# CarrierRecovery.net
KiCad netlist of a schematic drawn in Altium Designer
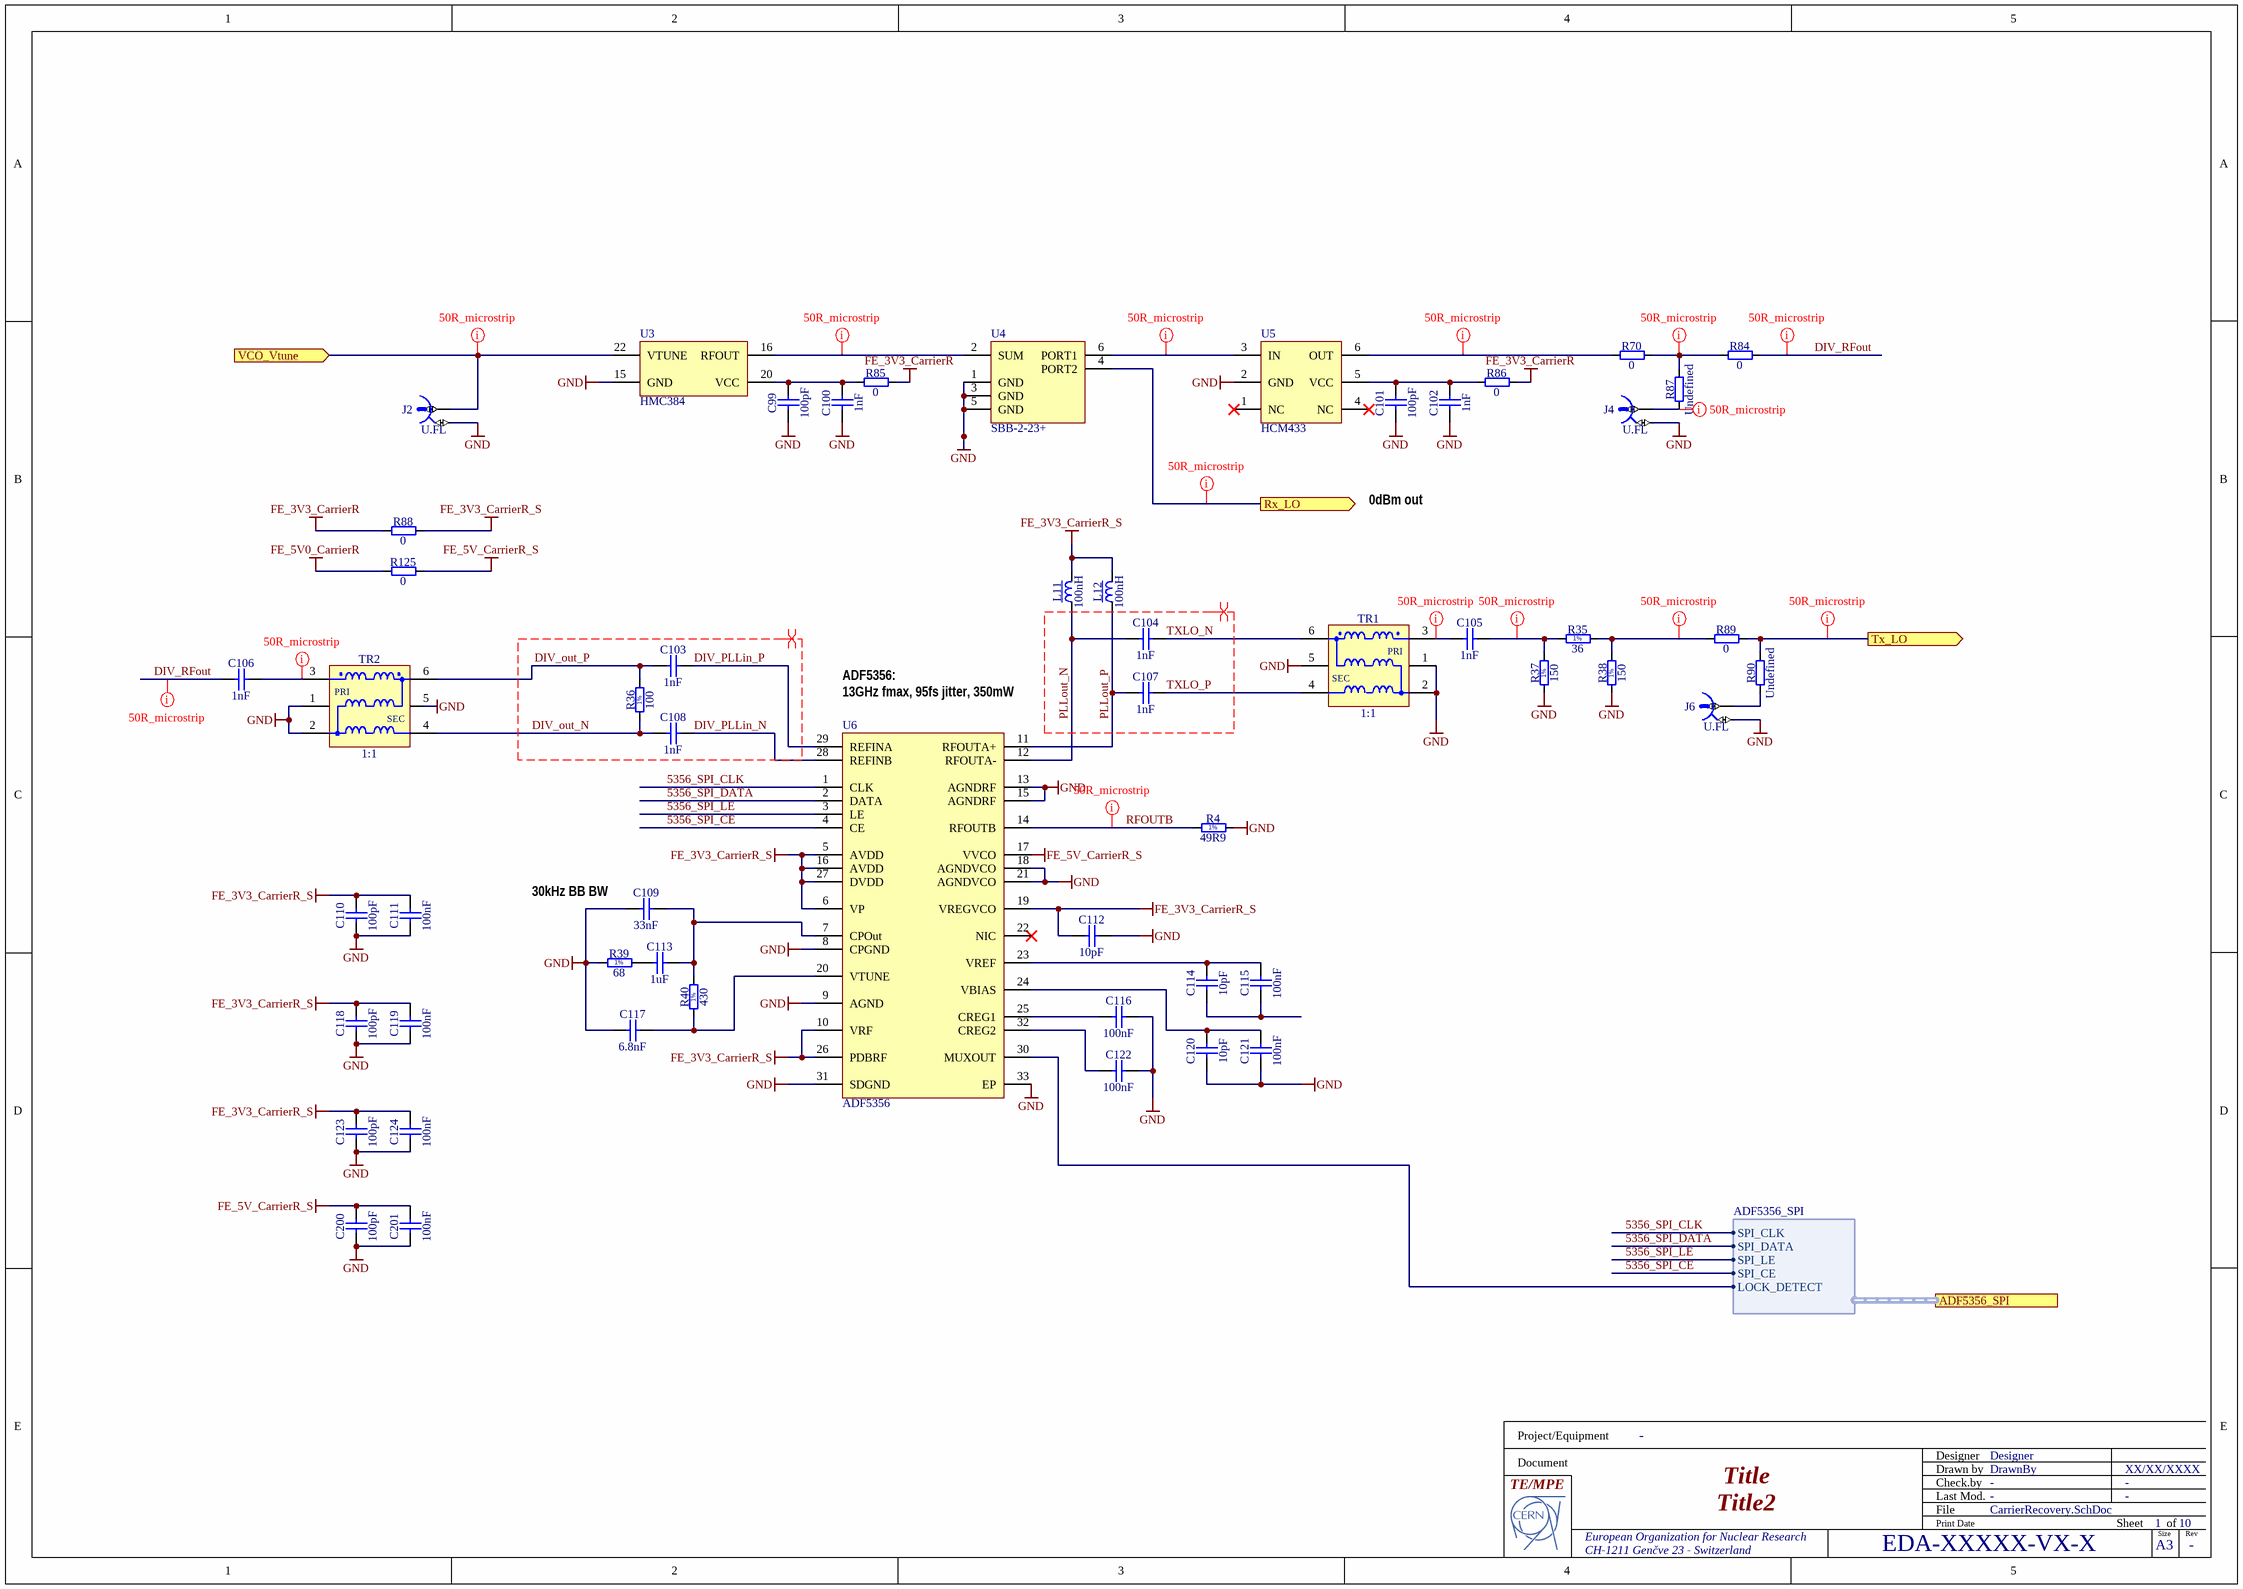
[diagram p0: CarrierRecovery.SchDoc]

(export (version "E")
  (design (tool "Eeschema 10.0.6"))
  (components
    (comp (ref "C99")
      (value "100pF")
      (footprint "CAPC1005X55N")
      (description "Non-polarised capacitor")
      (fields
        (field (name "PART NUMBER") "CC0402_100PF_50V_5%_C0G")
        (field (name "VOLTAGE") "50V")
        (field (name "AUTHOR") "CERN DEM JLC")
      )
      (libsource (lib "Capacitors") (part "Capacitor - non polarized"))
    )
    (comp (ref "C100")
      (value "1nF")
      (footprint "CAPC1005X55N")
      (description "Non-polarised capacitor")
      (fields
        (field (name "PART NUMBER") "CC0402_1NF_50V_10%_X7R")
        (field (name "VOLTAGE") "50V")
        (field (name "AUTHOR") "CERN DEM JLC")
      )
      (libsource (lib "Capacitors") (part "Capacitor - non polarized"))
    )
    (comp (ref "C101")
      (value "100pF")
      (footprint "CAPC1005X55N")
      (description "Non-polarised capacitor")
      (fields
        (field (name "PART NUMBER") "CC0402_100PF_50V_5%_C0G")
        (field (name "VOLTAGE") "50V")
        (field (name "AUTHOR") "CERN DEM JLC")
      )
      (libsource (lib "Capacitors") (part "Capacitor - non polarized"))
    )
    (comp (ref "C102")
      (value "1nF")
      (footprint "CAPC1005X55N")
      (description "Non-polarised capacitor")
      (fields
        (field (name "PART NUMBER") "CC0402_1NF_50V_10%_X7R")
        (field (name "VOLTAGE") "50V")
        (field (name "AUTHOR") "CERN DEM JLC")
      )
      (libsource (lib "Capacitors") (part "Capacitor - non polarized"))
    )
    (comp (ref "C103")
      (value "1nF")
      (footprint "CAPC1005X55N")
      (description "Non-polarised capacitor")
      (fields
        (field (name "PART NUMBER") "CC0402_1NF_50V_10%_X7R")
        (field (name "VOLTAGE") "50V")
        (field (name "AUTHOR") "CERN DEM JLC")
      )
      (libsource (lib "Capacitors") (part "Capacitor - non polarized"))
    )
    (comp (ref "C104")
      (value "1nF")
      (footprint "CAPC1005X55N")
      (description "Non-polarised capacitor")
      (fields
        (field (name "PART NUMBER") "CC0402_1NF_50V_10%_X7R")
        (field (name "VOLTAGE") "50V")
        (field (name "AUTHOR") "CERN DEM JLC")
      )
      (libsource (lib "Capacitors") (part "Capacitor - non polarized"))
    )
    (comp (ref "C105")
      (value "1nF")
      (footprint "CAPC1005X55N")
      (description "Non-polarised capacitor")
      (fields
        (field (name "PART NUMBER") "CC0402_1NF_50V_10%_X7R")
        (field (name "VOLTAGE") "50V")
        (field (name "AUTHOR") "CERN DEM JLC")
      )
      (libsource (lib "Capacitors") (part "Capacitor - non polarized"))
    )
    (comp (ref "C106")
      (value "1nF")
      (footprint "CAPC1005X55N")
      (description "Non-polarised capacitor")
      (fields
        (field (name "PART NUMBER") "CC0402_1NF_50V_10%_X7R")
        (field (name "VOLTAGE") "50V")
        (field (name "AUTHOR") "CERN DEM JLC")
      )
      (libsource (lib "Capacitors") (part "Capacitor - non polarized"))
    )
    (comp (ref "C107")
      (value "1nF")
      (footprint "CAPC1005X55N")
      (description "Non-polarised capacitor")
      (fields
        (field (name "PART NUMBER") "CC0402_1NF_50V_10%_X7R")
        (field (name "VOLTAGE") "50V")
        (field (name "AUTHOR") "CERN DEM JLC")
      )
      (libsource (lib "Capacitors") (part "Capacitor - non polarized"))
    )
    (comp (ref "C108")
      (value "1nF")
      (footprint "CAPC1005X55N")
      (description "Non-polarised capacitor")
      (fields
        (field (name "PART NUMBER") "CC0402_1NF_50V_10%_X7R")
        (field (name "VOLTAGE") "50V")
        (field (name "AUTHOR") "CERN DEM JLC")
      )
      (libsource (lib "Capacitors") (part "Capacitor - non polarized"))
    )
    (comp (ref "C109")
      (value "33nF")
      (footprint "CAPC2012X135N")
      (description "Non-polarised capacitor")
      (fields
        (field (name "PART NUMBER") "CC0805_33NF_25V_10%_X7R")
        (field (name "VOLTAGE") "25V")
        (field (name "AUTHOR") "CERN DEM JLC")
      )
      (libsource (lib "Capacitors") (part "Capacitor - non polarized"))
    )
    (comp (ref "C110")
      (value "100pF")
      (footprint "CAPC1005X55N")
      (description "Non-polarised capacitor")
      (fields
        (field (name "PART NUMBER") "CC0402_100PF_50V_5%_C0G")
        (field (name "VOLTAGE") "50V")
        (field (name "AUTHOR") "CERN DEM JLC")
      )
      (libsource (lib "Capacitors") (part "Capacitor - non polarized"))
    )
    (comp (ref "C111")
      (value "100nF")
      (footprint "CAPC1005X55N")
      (description "Non-polarised capacitor")
      (fields
        (field (name "PART NUMBER") "CC0402_100NF_50V_10%_X7R")
        (field (name "VOLTAGE") "50V")
        (field (name "AUTHOR") "CERN DEM MR")
      )
      (libsource (lib "Capacitors") (part "Capacitor - non polarized"))
    )
    (comp (ref "C112")
      (value "10pF")
      (footprint "CAPC1005X55N")
      (description "Non-polarised capacitor")
      (fields
        (field (name "PART NUMBER") "CC0402_10PF_50V_5%_C0G")
        (field (name "VOLTAGE") "50V")
        (field (name "AUTHOR") "CERN DEM JLC")
      )
      (libsource (lib "Capacitors") (part "Capacitor - non polarized"))
    )
    (comp (ref "C113")
      (value "1uF")
      (footprint "CAPC3216X140N")
      (description "Non-polarised capacitor")
      (fields
        (field (name "PART NUMBER") "CC1206_1UF_25V_10%_X7R")
        (field (name "VOLTAGE") "25V")
        (field (name "AUTHOR") "CERN DEM JLC")
      )
      (libsource (lib "Capacitors") (part "Capacitor - non polarized"))
    )
    (comp (ref "C114")
      (value "10pF")
      (footprint "CAPC1005X55N")
      (description "Non-polarised capacitor")
      (fields
        (field (name "PART NUMBER") "CC0402_10PF_50V_5%_C0G")
        (field (name "VOLTAGE") "50V")
        (field (name "AUTHOR") "CERN DEM JLC")
      )
      (libsource (lib "Capacitors") (part "Capacitor - non polarized"))
    )
    (comp (ref "C115")
      (value "100nF")
      (footprint "CAPC1005X55N")
      (description "Non-polarised capacitor")
      (fields
        (field (name "PART NUMBER") "CC0402_100NF_50V_10%_X7R")
        (field (name "VOLTAGE") "50V")
        (field (name "AUTHOR") "CERN DEM MR")
      )
      (libsource (lib "Capacitors") (part "Capacitor - non polarized"))
    )
    (comp (ref "C116")
      (value "100nF")
      (footprint "CAPC1005X55N")
      (description "Non-polarised capacitor")
      (fields
        (field (name "PART NUMBER") "CC0402_100NF_50V_10%_X7R")
        (field (name "VOLTAGE") "50V")
        (field (name "AUTHOR") "CERN DEM MR")
      )
      (libsource (lib "Capacitors") (part "Capacitor - non polarized"))
    )
    (comp (ref "C117")
      (value "6.8nF")
      (footprint "CAPC2012X135N")
      (description "Non-polarised capacitor")
      (fields
        (field (name "PART NUMBER") "CC0805_6.8NF_50V_10%_X7R")
        (field (name "VOLTAGE") "50V")
        (field (name "AUTHOR") "CERN DEM JLC")
      )
      (libsource (lib "Capacitors") (part "Capacitor - non polarized"))
    )
    (comp (ref "C118")
      (value "100pF")
      (footprint "CAPC1005X55N")
      (description "Non-polarised capacitor")
      (fields
        (field (name "PART NUMBER") "CC0402_100PF_50V_5%_C0G")
        (field (name "VOLTAGE") "50V")
        (field (name "AUTHOR") "CERN DEM JLC")
      )
      (libsource (lib "Capacitors") (part "Capacitor - non polarized"))
    )
    (comp (ref "C119")
      (value "100nF")
      (footprint "CAPC1005X55N")
      (description "Non-polarised capacitor")
      (fields
        (field (name "PART NUMBER") "CC0402_100NF_50V_10%_X7R")
        (field (name "VOLTAGE") "50V")
        (field (name "AUTHOR") "CERN DEM MR")
      )
      (libsource (lib "Capacitors") (part "Capacitor - non polarized"))
    )
    (comp (ref "C120")
      (value "10pF")
      (footprint "CAPC1005X55N")
      (description "Non-polarised capacitor")
      (fields
        (field (name "PART NUMBER") "CC0402_10PF_50V_5%_C0G")
        (field (name "VOLTAGE") "50V")
        (field (name "AUTHOR") "CERN DEM JLC")
      )
      (libsource (lib "Capacitors") (part "Capacitor - non polarized"))
    )
    (comp (ref "C121")
      (value "100nF")
      (footprint "CAPC1005X55N")
      (description "Non-polarised capacitor")
      (fields
        (field (name "PART NUMBER") "CC0402_100NF_50V_10%_X7R")
        (field (name "VOLTAGE") "50V")
        (field (name "AUTHOR") "CERN DEM MR")
      )
      (libsource (lib "Capacitors") (part "Capacitor - non polarized"))
    )
    (comp (ref "C122")
      (value "100nF")
      (footprint "CAPC1005X55N")
      (description "Non-polarised capacitor")
      (fields
        (field (name "PART NUMBER") "CC0402_100NF_50V_10%_X7R")
        (field (name "VOLTAGE") "50V")
        (field (name "AUTHOR") "CERN DEM MR")
      )
      (libsource (lib "Capacitors") (part "Capacitor - non polarized"))
    )
    (comp (ref "C123")
      (value "100pF")
      (footprint "CAPC1005X55N")
      (description "Non-polarised capacitor")
      (fields
        (field (name "PART NUMBER") "CC0402_100PF_50V_5%_C0G")
        (field (name "VOLTAGE") "50V")
        (field (name "AUTHOR") "CERN DEM JLC")
      )
      (libsource (lib "Capacitors") (part "Capacitor - non polarized"))
    )
    (comp (ref "C124")
      (value "100nF")
      (footprint "CAPC1005X55N")
      (description "Non-polarised capacitor")
      (fields
        (field (name "PART NUMBER") "CC0402_100NF_50V_10%_X7R")
        (field (name "VOLTAGE") "50V")
        (field (name "AUTHOR") "CERN DEM MR")
      )
      (libsource (lib "Capacitors") (part "Capacitor - non polarized"))
    )
    (comp (ref "C200")
      (value "100pF")
      (footprint "CAPC1005X55N")
      (description "Non-polarised capacitor")
      (fields
        (field (name "PART NUMBER") "CC0402_100PF_50V_5%_C0G")
        (field (name "VOLTAGE") "50V")
        (field (name "AUTHOR") "CERN DEM JLC")
      )
      (libsource (lib "Capacitors") (part "Capacitor - non polarized"))
    )
    (comp (ref "C201")
      (value "100nF")
      (footprint "CAPC1005X55N")
      (description "Non-polarised capacitor")
      (fields
        (field (name "PART NUMBER") "CC0402_100NF_50V_10%_X7R")
        (field (name "VOLTAGE") "50V")
        (field (name "AUTHOR") "CERN DEM MR")
      )
      (libsource (lib "Capacitors") (part "Capacitor - non polarized"))
    )
    (comp (ref "J2")
      (value "U.FL")
      (footprint "HIROSE_U.FL-R-SMT-1(10)")
      (fields
        (field (name "PART NUMBER") "HIROSE_U.FL-R-SMT-1(10)")
        (field (name "MANUFACTURER") "HIROSE (HRS)")
        (field (name "MANUFACTURER PART NUMBER") "U.FL-R-SMT-1(10)")
        (field (name "AUTHOR") "CERN DEM JLC")
      )
      (libsource (lib "Connectors") (part "Coax_1Male_1Shield"))
    )
    (comp (ref "J4")
      (value "U.FL")
      (footprint "HIROSE_U.FL-R-SMT-1(10)")
      (fields
        (field (name "PART NUMBER") "HIROSE_U.FL-R-SMT-1(10)")
        (field (name "MANUFACTURER") "HIROSE (HRS)")
        (field (name "MANUFACTURER PART NUMBER") "U.FL-R-SMT-1(10)")
        (field (name "AUTHOR") "CERN DEM JLC")
      )
      (libsource (lib "Connectors") (part "Coax_1Male_1Shield"))
    )
    (comp (ref "J6")
      (value "U.FL")
      (footprint "HIROSE_U.FL-R-SMT-1(10)")
      (fields
        (field (name "PART NUMBER") "HIROSE_U.FL-R-SMT-1(10)")
        (field (name "MANUFACTURER") "HIROSE (HRS)")
        (field (name "MANUFACTURER PART NUMBER") "U.FL-R-SMT-1(10)")
        (field (name "AUTHOR") "CERN DEM JLC")
      )
      (libsource (lib "Connectors") (part "Coax_1Male_1Shield"))
    )
    (comp (ref "L11")
      (value "100nH")
      (footprint "IND_COILCRAFT_0603HP")
      (description "Inductor With Core")
      (fields
        (field (name "PART NUMBER") "IND0603_100NH_2%_COILCRAFT_0603HP-R10XGLU")
        (field (name "POWER") "470mA")
        (field (name "AUTHOR") "CERN DEM JLC")
      )
      (libsource (lib "Inductors & Transformers") (part "Inductor With Magnetic core"))
    )
    (comp (ref "L12")
      (value "100nH")
      (footprint "IND_COILCRAFT_0603HP")
      (description "Inductor With Core")
      (fields
        (field (name "PART NUMBER") "IND0603_100NH_2%_COILCRAFT_0603HP-R10XGLU")
        (field (name "POWER") "470mA")
        (field (name "AUTHOR") "CERN DEM JLC")
      )
      (libsource (lib "Inductors & Transformers") (part "Inductor With Magnetic core"))
    )
    (comp (ref "R4")
      (value "49R9")
      (footprint "RESC1005X40N")
      (description "Resistor - 1%")
      (fields
        (field (name "PART NUMBER") "R0402_49R9_1%_0.0625W_100PPM")
        (field (name "POWER") "0.0625W")
        (field (name "AUTHOR") "CERN DEM JLC")
      )
      (libsource (lib "Resistors") (part "Resistor - 1%"))
    )
    (comp (ref "R35")
      (value "36")
      (footprint "RESC1005X40N")
      (description "Resistor - 1%")
      (fields
        (field (name "PART NUMBER") "R0402_36R_1%_0.0625W_100PPM")
        (field (name "POWER") "0.0625W")
        (field (name "AUTHOR") "CERN DEM JLC")
      )
      (libsource (lib "Resistors") (part "Resistor - 1%"))
    )
    (comp (ref "R36")
      (value "100")
      (footprint "RESC1005X40N")
      (description "Resistor - 1%")
      (fields
        (field (name "PART NUMBER") "R0402_100R_1%_0.0625W_100PPM")
        (field (name "POWER") "0.0625W")
        (field (name "AUTHOR") "CERN DEM JLC")
      )
      (libsource (lib "Resistors") (part "Resistor - 1%"))
    )
    (comp (ref "R37")
      (value "150")
      (footprint "RESC1005X40N")
      (description "Resistor - 1%")
      (fields
        (field (name "PART NUMBER") "R0402_150R_1%_0.0625W_100PPM")
        (field (name "POWER") "0.0625W")
        (field (name "AUTHOR") "CERN DEM JLC")
      )
      (libsource (lib "Resistors") (part "Resistor - 1%"))
    )
    (comp (ref "R38")
      (value "150")
      (footprint "RESC1005X40N")
      (description "Resistor - 1%")
      (fields
        (field (name "PART NUMBER") "R0402_150R_1%_0.0625W_100PPM")
        (field (name "POWER") "0.0625W")
        (field (name "AUTHOR") "CERN DEM JLC")
      )
      (libsource (lib "Resistors") (part "Resistor - 1%"))
    )
    (comp (ref "R39")
      (value "68")
      (footprint "RESC1608X55N")
      (description "Resistor - 1%")
      (fields
        (field (name "PART NUMBER") "R0603_68R_1%_0.1W_100PPM")
        (field (name "POWER") "0.1W")
        (field (name "AUTHOR") "CERN DEM JLC")
      )
      (libsource (lib "Resistors") (part "Resistor - 1%"))
    )
    (comp (ref "R40")
      (value "430")
      (footprint "RESC1608X55N")
      (description "Resistor - 1%")
      (fields
        (field (name "PART NUMBER") "R0603_430R_1%_0.1W_100PPM")
        (field (name "POWER") "0.1W")
        (field (name "AUTHOR") "CERN DEM JLC")
      )
      (libsource (lib "Resistors") (part "Resistor - 1%"))
    )
    (comp (ref "R70")
      (value "0")
      (footprint "RESC1608X55N")
      (description "Resistor")
      (fields
        (field (name "PART NUMBER") "R0603_0R_JUMPER")
        (field (name "MANUFACTURER") "GENERIC")
        (field (name "AUTHOR") "CERN DEM JLC")
      )
      (libsource (lib "Resistors") (part "Resistor"))
    )
    (comp (ref "R84")
      (value "0")
      (footprint "RESC1608X55N")
      (description "Resistor")
      (fields
        (field (name "PART NUMBER") "R0603_0R_JUMPER")
        (field (name "MANUFACTURER") "GENERIC")
        (field (name "AUTHOR") "CERN DEM JLC")
      )
      (libsource (lib "Resistors") (part "Resistor"))
    )
    (comp (ref "R85")
      (value "0")
      (footprint "RESC1608X55N")
      (description "Resistor")
      (fields
        (field (name "PART NUMBER") "R0603_0R_JUMPER")
        (field (name "MANUFACTURER") "GENERIC")
        (field (name "AUTHOR") "CERN DEM JLC")
      )
      (libsource (lib "Resistors") (part "Resistor"))
    )
    (comp (ref "R86")
      (value "0")
      (footprint "RESC1608X55N")
      (description "Resistor")
      (fields
        (field (name "PART NUMBER") "R0603_0R_JUMPER")
        (field (name "MANUFACTURER") "GENERIC")
        (field (name "AUTHOR") "CERN DEM JLC")
      )
      (libsource (lib "Resistors") (part "Resistor"))
    )
    (comp (ref "R87")
      (value "Undefined")
      (footprint "RESC1608X55N")
      (description "Resistor")
      (fields (field (name "PART NUMBER") "R0603_NO-VALUE") (field (name "AUTHOR") "CERN DEM JLC"))
      (libsource (lib "Resistors") (part "Resistor"))
    )
    (comp (ref "R88")
      (value "0")
      (footprint "RESC1608X55N")
      (description "Resistor")
      (fields
        (field (name "PART NUMBER") "R0603_0R_JUMPER")
        (field (name "MANUFACTURER") "GENERIC")
        (field (name "AUTHOR") "CERN DEM JLC")
      )
      (libsource (lib "Resistors") (part "Resistor"))
    )
    (comp (ref "R89")
      (value "0")
      (footprint "RESC1608X55N")
      (description "Resistor")
      (fields
        (field (name "PART NUMBER") "R0603_0R_JUMPER")
        (field (name "MANUFACTURER") "GENERIC")
        (field (name "AUTHOR") "CERN DEM JLC")
      )
      (libsource (lib "Resistors") (part "Resistor"))
    )
    (comp (ref "R90")
      (value "Undefined")
      (footprint "RESC1608X55N")
      (description "Resistor")
      (fields (field (name "PART NUMBER") "R0603_NO-VALUE") (field (name "AUTHOR") "CERN DEM JLC"))
      (libsource (lib "Resistors") (part "Resistor"))
    )
    (comp (ref "R125")
      (value "0")
      (footprint "RESC1608X55N")
      (description "Resistor")
      (fields
        (field (name "PART NUMBER") "R0603_0R_JUMPER")
        (field (name "MANUFACTURER") "GENERIC")
        (field (name "AUTHOR") "CERN DEM JLC")
      )
      (libsource (lib "Resistors") (part "Resistor"))
    )
    (comp (ref "TR1")
      (value "1:1")
      (footprint "XFMR_MINI-CIRCUITS_DB1627")
      (description "50 Ohms 10  to 6000MHz RF Transformer")
      (fields
        (field (name "PART NUMBER") "XFMR_MINI-CIRCUITS_TCM1-63AX+")
        (field (name "POWER") "0.2W")
        (field (name "AUTHOR") "CERN DEM MR")
      )
      (libsource (lib "") (part "XFMR_MINI-CIRCUITS_TCM1-63AX+_1"))
    )
    (comp (ref "TR2")
      (value "1:1")
      (footprint "XFMR_MINI-CIRCUITS_DB1627")
      (description "50 Ohms 10  to 6000MHz RF Transformer")
      (fields
        (field (name "PART NUMBER") "XFMR_MINI-CIRCUITS_TCM1-63AX+")
        (field (name "POWER") "0.2W")
        (field (name "AUTHOR") "CERN DEM MR")
      )
      (libsource (lib "Inductors & Transformers") (part "XFMR_MINI-CIRCUITS_TCM1-63AX+"))
    )
    (comp (ref "U3") (value "HMC384") (footprint "HMC384") (libsource (lib "FMC_SDR") (part "HMC384")))
    (comp (ref "U4")
      (value "SBB-2-23+")
      (footprint "SBB-2-23")
      (libsource (lib "FMC_SDR") (part "SBB-2-23+"))
    )
    (comp (ref "U5") (value "HCM433") (footprint "HMC433") (libsource (lib "FMC_SDR") (part "HCM433")))
    (comp (ref "U6") (value "ADF5356") (footprint "ADF3356") (libsource (lib "FMC_SDR") (part "ADF5356")))
  )
  (nets
    (net (code "2") (name "/5356_SPI_CE") (class "Default")
      (node (ref "U6") (pin "4") (pinfunction "CE_4") (pintype "passive"))
    )
    (net (code "3") (name "/5356_SPI_CLK") (class "Default")
      (node (ref "U6") (pin "1") (pinfunction "CLK_1") (pintype "passive"))
    )
    (net (code "4") (name "/5356_SPI_DATA") (class "Default")
      (node (ref "U6") (pin "2") (pinfunction "DATA_2") (pintype "passive"))
    )
    (net (code "5") (name "/5356_SPI_LE") (class "Default")
      (node (ref "U6") (pin "3") (pinfunction "LE_3") (pintype "passive"))
    )
    (net (code "6") (name "/DIV_PLLin_N") (class "Default")
      (node (ref "C108") (pin "2") (pinfunction "2_2") (pintype "passive"))
      (node (ref "U6") (pin "28") (pinfunction "REFINB_28") (pintype "passive"))
    )
    (net (code "7") (name "/DIV_PLLin_P") (class "Default")
      (node (ref "C103") (pin "2") (pinfunction "2_2") (pintype "passive"))
      (node (ref "U6") (pin "29") (pinfunction "REFINA_29") (pintype "passive"))
    )
    (net (code "8") (name "/DIV_RFout") (class "Default")
      (node (ref "C106") (pin "1") (pinfunction "1_1") (pintype "passive"))
      (node (ref "R84") (pin "2") (pinfunction "2_2") (pintype "passive"))
    )
    (net (code "9") (name "/DIV_out_N") (class "Default")
      (node (ref "C108") (pin "1") (pinfunction "1_1") (pintype "passive"))
      (node (ref "R36") (pin "1") (pinfunction "1_1") (pintype "passive"))
      (node (ref "TR2") (pin "4") (pinfunction "S1_4") (pintype "passive"))
    )
    (net (code "10") (name "/DIV_out_P") (class "Default")
      (node (ref "C103") (pin "1") (pinfunction "1_1") (pintype "passive"))
      (node (ref "R36") (pin "2") (pinfunction "2_2") (pintype "passive"))
      (node (ref "TR2") (pin "6") (pinfunction "S1_6") (pintype "passive"))
    )
    (net (code "11") (name "/LOCK_DETECT") (class "Default")
      (node (ref "U6") (pin "30") (pinfunction "MUXOUT_30") (pintype "passive"))
    )
    (net (code "12") (name "/PLLout_N") (class "Default")
      (node (ref "C104") (pin "1") (pinfunction "1_1") (pintype "passive"))
      (node (ref "L11") (pin "1") (pinfunction "1_1") (pintype "passive"))
      (node (ref "U6") (pin "12") (pinfunction "RFOUTA-_12") (pintype "passive"))
    )
    (net (code "13") (name "/PLLout_P") (class "Default")
      (node (ref "C107") (pin "1") (pinfunction "1_1") (pintype "passive"))
      (node (ref "L12") (pin "1") (pinfunction "1_1") (pintype "passive"))
      (node (ref "U6") (pin "11") (pinfunction "RFOUTA+_11") (pintype "passive"))
    )
    (net (code "14") (name "/RFOUTB") (class "Default")
      (node (ref "R4") (pin "1") (pinfunction "1_1") (pintype "passive"))
      (node (ref "U6") (pin "14") (pinfunction "RFOUTB_14") (pintype "passive"))
    )
    (net (code "15") (name "/Rx_LO") (class "Default")
      (node (ref "U4") (pin "4") (pinfunction "PORT2_4") (pintype "passive"))
    )
    (net (code "16") (name "/TXLO_N") (class "Default")
      (node (ref "C104") (pin "2") (pinfunction "2_2") (pintype "passive"))
      (node (ref "TR1") (pin "6") (pinfunction "S1_6") (pintype "passive"))
    )
    (net (code "17") (name "/TXLO_P") (class "Default")
      (node (ref "C107") (pin "2") (pinfunction "2_2") (pintype "passive"))
      (node (ref "TR1") (pin "4") (pinfunction "S1_4") (pintype "passive"))
    )
    (net (code "18") (name "/Tx_LO") (class "Default")
      (node (ref "R89") (pin "2") (pinfunction "2_2") (pintype "passive"))
      (node (ref "R90") (pin "2") (pinfunction "2_2") (pintype "passive"))
    )
    (net (code "19") (name "/VCO_Vtune") (class "Default")
      (node (ref "J2") (pin "1") (pinfunction "1_1") (pintype "bidirectional"))
      (node (ref "U3") (pin "22") (pinfunction "VTUNE_22") (pintype "passive"))
    )
    (net (code "21") (name "FE_3V3_CarrierR") (class "Default")
      (node (ref "R85") (pin "2") (pinfunction "2_2") (pintype "passive"))
      (node (ref "R86") (pin "2") (pinfunction "2_2") (pintype "passive"))
      (node (ref "R88") (pin "1") (pinfunction "1_1") (pintype "passive"))
    )
    (net (code "22") (name "FE_3V3_CarrierR_S") (class "Default")
      (node (ref "C110") (pin "2") (pinfunction "2_2") (pintype "passive"))
      (node (ref "C111") (pin "2") (pinfunction "2_2") (pintype "passive"))
      (node (ref "C112") (pin "1") (pinfunction "1_1") (pintype "passive"))
      (node (ref "C118") (pin "2") (pinfunction "2_2") (pintype "passive"))
      (node (ref "C119") (pin "2") (pinfunction "2_2") (pintype "passive"))
      (node (ref "C123") (pin "2") (pinfunction "2_2") (pintype "passive"))
      (node (ref "C124") (pin "2") (pinfunction "2_2") (pintype "passive"))
      (node (ref "L11") (pin "2") (pinfunction "2_2") (pintype "passive"))
      (node (ref "L12") (pin "2") (pinfunction "2_2") (pintype "passive"))
      (node (ref "R88") (pin "2") (pinfunction "2_2") (pintype "passive"))
      (node (ref "U6") (pin "10") (pinfunction "VRF_10") (pintype "passive"))
      (node (ref "U6") (pin "16") (pinfunction "AVDD_16") (pintype "passive"))
      (node (ref "U6") (pin "19") (pinfunction "VREGVCO_19") (pintype "passive"))
      (node (ref "U6") (pin "26") (pinfunction "PDBRF_26") (pintype "passive"))
      (node (ref "U6") (pin "27") (pinfunction "DVDD_27") (pintype "passive"))
      (node (ref "U6") (pin "5") (pinfunction "AVDD_5") (pintype "passive"))
      (node (ref "U6") (pin "6") (pinfunction "VP_6") (pintype "passive"))
    )
    (net (code "23") (name "FE_5V0_CarrierR") (class "Default")
      (node (ref "R125") (pin "1") (pinfunction "1_1") (pintype "passive"))
    )
    (net (code "24") (name "FE_5V_CarrierR_S") (class "Default")
      (node (ref "C200") (pin "2") (pinfunction "2_2") (pintype "passive"))
      (node (ref "C201") (pin "2") (pinfunction "2_2") (pintype "passive"))
      (node (ref "R125") (pin "2") (pinfunction "2_2") (pintype "passive"))
      (node (ref "U6") (pin "17") (pinfunction "VVCO_17") (pintype "passive"))
    )
    (net (code "25") (name "GND") (class "Default")
      (node (ref "C100") (pin "1") (pinfunction "1_1") (pintype "passive"))
      (node (ref "C101") (pin "1") (pinfunction "1_1") (pintype "passive"))
      (node (ref "C102") (pin "1") (pinfunction "1_1") (pintype "passive"))
      (node (ref "C109") (pin "1") (pinfunction "1_1") (pintype "passive"))
      (node (ref "C110") (pin "1") (pinfunction "1_1") (pintype "passive"))
      (node (ref "C111") (pin "1") (pinfunction "1_1") (pintype "passive"))
      (node (ref "C112") (pin "2") (pinfunction "2_2") (pintype "passive"))
      (node (ref "C116") (pin "2") (pinfunction "2_2") (pintype "passive"))
      (node (ref "C117") (pin "1") (pinfunction "1_1") (pintype "passive"))
      (node (ref "C118") (pin "1") (pinfunction "1_1") (pintype "passive"))
      (node (ref "C119") (pin "1") (pinfunction "1_1") (pintype "passive"))
      (node (ref "C120") (pin "1") (pinfunction "1_1") (pintype "passive"))
      (node (ref "C121") (pin "1") (pinfunction "1_1") (pintype "passive"))
      (node (ref "C122") (pin "2") (pinfunction "2_2") (pintype "passive"))
      (node (ref "C123") (pin "1") (pinfunction "1_1") (pintype "passive"))
      (node (ref "C124") (pin "1") (pinfunction "1_1") (pintype "passive"))
      (node (ref "C200") (pin "1") (pinfunction "1_1") (pintype "passive"))
      (node (ref "C201") (pin "1") (pinfunction "1_1") (pintype "passive"))
      (node (ref "C99") (pin "1") (pinfunction "1_1") (pintype "passive"))
      (node (ref "J2") (pin "2") (pinfunction "2_2") (pintype "bidirectional"))
      (node (ref "J4") (pin "2") (pinfunction "2_2") (pintype "bidirectional"))
      (node (ref "J6") (pin "2") (pinfunction "2_2") (pintype "bidirectional"))
      (node (ref "R37") (pin "1") (pinfunction "1_1") (pintype "passive"))
      (node (ref "R38") (pin "1") (pinfunction "1_1") (pintype "passive"))
      (node (ref "R39") (pin "1") (pinfunction "1_1") (pintype "passive"))
      (node (ref "R4") (pin "2") (pinfunction "2_2") (pintype "passive"))
      (node (ref "TR1") (pin "1") (pinfunction "NC_1") (pintype "passive"))
      (node (ref "TR1") (pin "2") (pinfunction "P1_2") (pintype "passive"))
      (node (ref "TR1") (pin "5") (pinfunction "NC_5") (pintype "passive"))
      (node (ref "TR2") (pin "1") (pinfunction "NC_1") (pintype "passive"))
      (node (ref "TR2") (pin "2") (pinfunction "P1_2") (pintype "passive"))
      (node (ref "TR2") (pin "5") (pinfunction "NC_5") (pintype "passive"))
      (node (ref "U3") (pin "15") (pinfunction "GND_15") (pintype "passive"))
      (node (ref "U4") (pin "1") (pinfunction "GND_1") (pintype "passive"))
      (node (ref "U4") (pin "3") (pinfunction "GND_3") (pintype "passive"))
      (node (ref "U4") (pin "5") (pinfunction "GND_5") (pintype "passive"))
      (node (ref "U5") (pin "2") (pinfunction "GND_2") (pintype "passive"))
      (node (ref "U6") (pin "13") (pinfunction "AGNDRF_13") (pintype "passive"))
      (node (ref "U6") (pin "15") (pinfunction "AGNDRF_15") (pintype "passive"))
      (node (ref "U6") (pin "18") (pinfunction "AGNDVCO_18") (pintype "passive"))
      (node (ref "U6") (pin "21") (pinfunction "AGNDVCO_21") (pintype "passive"))
      (node (ref "U6") (pin "31") (pinfunction "SDGND_31") (pintype "passive"))
      (node (ref "U6") (pin "33") (pinfunction "EP_33") (pintype "passive"))
      (node (ref "U6") (pin "8") (pinfunction "CPGND_8") (pintype "passive"))
      (node (ref "U6") (pin "9") (pinfunction "AGND_9") (pintype "passive"))
    )
    (net (code "26") (name "Net-(C105-Pad1)") (class "Default")
      (node (ref "C105") (pin "1") (pinfunction "1_1") (pintype "passive"))
      (node (ref "TR1") (pin "3") (pinfunction "P1_3") (pintype "passive"))
    )
    (net (code "27") (name "Net-(C105-Pad2)") (class "Default")
      (node (ref "C105") (pin "2") (pinfunction "2_2") (pintype "passive"))
      (node (ref "R35") (pin "1") (pinfunction "1_1") (pintype "passive"))
      (node (ref "R37") (pin "2") (pinfunction "2_2") (pintype "passive"))
    )
    (net (code "28") (name "Net-(C106-Pad2)") (class "Default")
      (node (ref "C106") (pin "2") (pinfunction "2_2") (pintype "passive"))
      (node (ref "TR2") (pin "3") (pinfunction "P1_3") (pintype "passive"))
    )
    (net (code "29") (name "Net-(C113-Pad1)") (class "Default")
      (node (ref "C113") (pin "1") (pinfunction "1_1") (pintype "passive"))
      (node (ref "R39") (pin "2") (pinfunction "2_2") (pintype "passive"))
    )
    (net (code "30") (name "Net-(C114-Pad1)") (class "Default")
      (node (ref "C114") (pin "1") (pinfunction "1_1") (pintype "passive"))
      (node (ref "C115") (pin "1") (pinfunction "1_1") (pintype "passive"))
    )
    (net (code "31") (name "Net-(J4-Pad1)") (class "Default")
      (node (ref "J4") (pin "1") (pinfunction "1_1") (pintype "bidirectional"))
      (node (ref "R87") (pin "1") (pinfunction "1_1") (pintype "passive"))
    )
    (net (code "32") (name "Net-(J6-Pad1)") (class "Default")
      (node (ref "J6") (pin "1") (pinfunction "1_1") (pintype "bidirectional"))
      (node (ref "R90") (pin "1") (pinfunction "1_1") (pintype "passive"))
    )
    (net (code "33") (name "Net-(R35-Pad2)") (class "Default")
      (node (ref "R35") (pin "2") (pinfunction "2_2") (pintype "passive"))
      (node (ref "R38") (pin "2") (pinfunction "2_2") (pintype "passive"))
      (node (ref "R89") (pin "1") (pinfunction "1_1") (pintype "passive"))
    )
    (net (code "34") (name "Net-(R70-Pad2)") (class "Default")
      (node (ref "R70") (pin "2") (pinfunction "2_2") (pintype "passive"))
      (node (ref "R84") (pin "1") (pinfunction "1_1") (pintype "passive"))
      (node (ref "R87") (pin "2") (pinfunction "2_2") (pintype "passive"))
    )
    (net (code "35") (name "Net-(U3-RFOUT)") (class "Default")
      (node (ref "U3") (pin "16") (pinfunction "RFOUT_16") (pintype "passive"))
      (node (ref "U4") (pin "2") (pinfunction "SUM_2") (pintype "passive"))
    )
    (net (code "36") (name "Net-(U3-VCC)") (class "Default")
      (node (ref "C100") (pin "2") (pinfunction "2_2") (pintype "passive"))
      (node (ref "C99") (pin "2") (pinfunction "2_2") (pintype "passive"))
      (node (ref "R85") (pin "1") (pinfunction "1_1") (pintype "passive"))
      (node (ref "U3") (pin "20") (pinfunction "VCC_20") (pintype "passive"))
    )
    (net (code "37") (name "Net-(U4-PORT1)") (class "Default")
      (node (ref "U4") (pin "6") (pinfunction "PORT1_6") (pintype "passive"))
      (node (ref "U5") (pin "3") (pinfunction "IN_3") (pintype "passive"))
    )
    (net (code "38") (name "Net-(U5-OUT)") (class "Default")
      (node (ref "R70") (pin "1") (pinfunction "1_1") (pintype "passive"))
      (node (ref "U5") (pin "6") (pinfunction "OUT_6") (pintype "passive"))
    )
    (net (code "39") (name "Net-(U5-VCC)") (class "Default")
      (node (ref "C101") (pin "2") (pinfunction "2_2") (pintype "passive"))
      (node (ref "C102") (pin "2") (pinfunction "2_2") (pintype "passive"))
      (node (ref "R86") (pin "1") (pinfunction "1_1") (pintype "passive"))
      (node (ref "U5") (pin "5") (pinfunction "VCC_5") (pintype "passive"))
    )
    (net (code "40") (name "Net-(U6-CPOut)") (class "Default")
      (node (ref "C109") (pin "2") (pinfunction "2_2") (pintype "passive"))
      (node (ref "C113") (pin "2") (pinfunction "2_2") (pintype "passive"))
      (node (ref "R40") (pin "2") (pinfunction "2_2") (pintype "passive"))
      (node (ref "U6") (pin "7") (pinfunction "CPOut_7") (pintype "passive"))
    )
    (net (code "41") (name "Net-(U6-CREG1)") (class "Default")
      (node (ref "C116") (pin "1") (pinfunction "1_1") (pintype "passive"))
      (node (ref "U6") (pin "25") (pinfunction "CREG1_25") (pintype "passive"))
    )
    (net (code "42") (name "Net-(U6-CREG2)") (class "Default")
      (node (ref "C122") (pin "1") (pinfunction "1_1") (pintype "passive"))
      (node (ref "U6") (pin "32") (pinfunction "CREG2_32") (pintype "passive"))
    )
    (net (code "43") (name "Net-(U6-VBIAS)") (class "Default")
      (node (ref "C120") (pin "2") (pinfunction "2_2") (pintype "passive"))
      (node (ref "C121") (pin "2") (pinfunction "2_2") (pintype "passive"))
      (node (ref "U6") (pin "24") (pinfunction "VBIAS_24") (pintype "passive"))
    )
    (net (code "44") (name "Net-(U6-VREF)") (class "Default")
      (node (ref "C114") (pin "2") (pinfunction "2_2") (pintype "passive"))
      (node (ref "C115") (pin "2") (pinfunction "2_2") (pintype "passive"))
      (node (ref "U6") (pin "23") (pinfunction "VREF_23") (pintype "passive"))
    )
    (net (code "45") (name "Net-(U6-VTUNE)") (class "Default")
      (node (ref "C117") (pin "2") (pinfunction "2_2") (pintype "passive"))
      (node (ref "R40") (pin "1") (pinfunction "1_1") (pintype "passive"))
      (node (ref "U6") (pin "20") (pinfunction "VTUNE_20") (pintype "passive"))
    )
    (net (code "46") (name "unconnected-(U5-NC-Pad1)") (class "Default")
      (node (ref "U5") (pin "1") (pinfunction "NC_1") (pintype "passive+no_connect"))
    )
    (net (code "47") (name "unconnected-(U5-NC-Pad4)") (class "Default")
      (node (ref "U5") (pin "4") (pinfunction "NC_4") (pintype "passive+no_connect"))
    )
    (net (code "48") (name "unconnected-(U6-NIC-Pad22)") (class "Default")
      (node (ref "U6") (pin "22") (pinfunction "NIC_22") (pintype "passive+no_connect"))
    )
  )
)
